# 1_1.net
KiCad netlist of a schematic drawn in Altium Designer
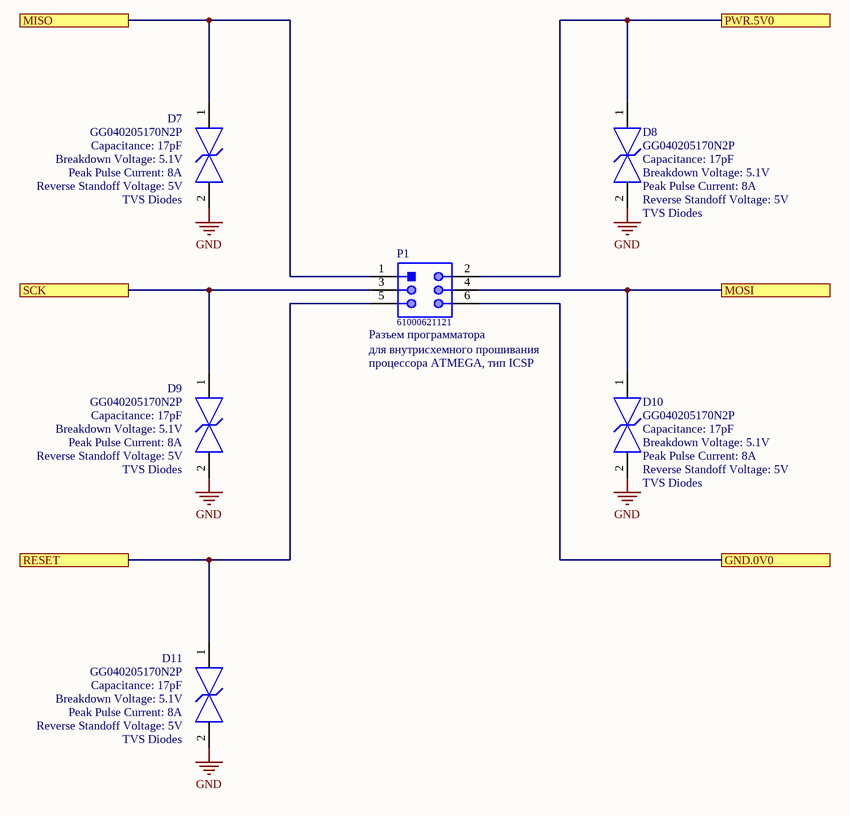
[diagram p0: Блок1.1.SchDoc]

(export (version "E")
  (design (tool "Eeschema 10.0.6"))
  (components
    (comp (ref "D7")
      (value "GG040205170N2P")
      (footprint "FP-GG0402-IPC_A")
      (description "TVS DIODE 5V 10V 0402")
      (fields
        (field (name "OCTOPART") "https://octopart.com/gg040205170n2p-avx-81066082")
        (field (name "CAPACITANCE") "17pF")
        (field (name "MANUFACTURER") "AVX")
        (field (name "BREAKDOWN VOLTAGE") "5.1V")
        (field (name "PEAK PULSE CURRENT") "8A")
        (field (name "REVERSE STANDOFF VOLTAGE") "5V")
        (field (name "DEVICE CLASS L2") "TVS Diodes")
      )
      (libsource (lib "Altium Content Vault") (part "11bd9d59d340f0612179daf16ad9b72"))
    )
    (comp (ref "D8")
      (value "GG040205170N2P")
      (footprint "FP-GG0402-IPC_A")
      (description "TVS DIODE 5V 10V 0402")
      (fields
        (field (name "OCTOPART") "https://octopart.com/gg040205170n2p-avx-81066082")
        (field (name "CAPACITANCE") "17pF")
        (field (name "MANUFACTURER") "AVX")
        (field (name "BREAKDOWN VOLTAGE") "5.1V")
        (field (name "PEAK PULSE CURRENT") "8A")
        (field (name "REVERSE STANDOFF VOLTAGE") "5V")
        (field (name "DEVICE CLASS L2") "TVS Diodes")
      )
      (libsource (lib "Altium Content Vault") (part "11bd9d59d340f0612179daf16ad9b72"))
    )
    (comp (ref "D9")
      (value "GG040205170N2P")
      (footprint "FP-GG0402-IPC_A")
      (description "TVS DIODE 5V 10V 0402")
      (fields
        (field (name "OCTOPART") "https://octopart.com/gg040205170n2p-avx-81066082")
        (field (name "CAPACITANCE") "17pF")
        (field (name "MANUFACTURER") "AVX")
        (field (name "BREAKDOWN VOLTAGE") "5.1V")
        (field (name "PEAK PULSE CURRENT") "8A")
        (field (name "REVERSE STANDOFF VOLTAGE") "5V")
        (field (name "DEVICE CLASS L2") "TVS Diodes")
      )
      (libsource (lib "Altium Content Vault") (part "11bd9d59d340f0612179daf16ad9b72"))
    )
    (comp (ref "D10")
      (value "GG040205170N2P")
      (footprint "FP-GG0402-IPC_A")
      (description "TVS DIODE 5V 10V 0402")
      (fields
        (field (name "OCTOPART") "https://octopart.com/gg040205170n2p-avx-81066082")
        (field (name "CAPACITANCE") "17pF")
        (field (name "MANUFACTURER") "AVX")
        (field (name "BREAKDOWN VOLTAGE") "5.1V")
        (field (name "PEAK PULSE CURRENT") "8A")
        (field (name "REVERSE STANDOFF VOLTAGE") "5V")
        (field (name "DEVICE CLASS L2") "TVS Diodes")
      )
      (libsource (lib "Altium Content Vault") (part "11bd9d59d340f0612179daf16ad9b72"))
    )
    (comp (ref "D11")
      (value "GG040205170N2P")
      (footprint "FP-GG0402-IPC_A")
      (description "TVS DIODE 5V 10V 0402")
      (fields
        (field (name "OCTOPART") "https://octopart.com/gg040205170n2p-avx-81066082")
        (field (name "CAPACITANCE") "17pF")
        (field (name "MANUFACTURER") "AVX")
        (field (name "BREAKDOWN VOLTAGE") "5.1V")
        (field (name "PEAK PULSE CURRENT") "8A")
        (field (name "REVERSE STANDOFF VOLTAGE") "5V")
        (field (name "DEVICE CLASS L2") "TVS Diodes")
      )
      (libsource (lib "Altium Content Vault") (part "11bd9d59d340f0612179daf16ad9b72"))
    )
    (comp (ref "P1")
      (value "61000621121")
      (footprint "61000621121")
      (description "SMT Vertical Pin Header WR-PHD, Pitch 2.54 mm, Dual Row, 6 pins")
      (fields
        (field (name "MANUFACTURER") "Wurth Elektronik")
        (field (name "PARAMETER 1") "Разъем программатора")
        (field (name "PARAMETER 2") "для внутрисхемного прошивания")
        (field (name "PARAMETER 3") "процессора ATMEGA, тип ICSP")
        (field (name "PUBLISHER") "WurthElektronik")
      )
      (libsource (lib "Altium Content Vault") (part "WE-CN-2P-M-R6"))
    )
  )
  (nets
    (net (code "1") (name "/GND.0V0") (class "Default")
      (node (ref "P1") (pin "6") (pinfunction "6_6") (pintype "passive"))
    )
    (net (code "2") (name "/MISO") (class "Default")
      (node (ref "D7") (pin "1") (pinfunction "1_1") (pintype "passive"))
      (node (ref "P1") (pin "1") (pinfunction "1_1") (pintype "passive"))
    )
    (net (code "3") (name "/MOSI") (class "Default")
      (node (ref "D10") (pin "1") (pinfunction "1_1") (pintype "passive"))
      (node (ref "P1") (pin "4") (pinfunction "4_4") (pintype "passive"))
    )
    (net (code "4") (name "/PWR.5V0") (class "Default")
      (node (ref "D8") (pin "1") (pinfunction "1_1") (pintype "passive"))
      (node (ref "P1") (pin "2") (pinfunction "2_2") (pintype "passive"))
    )
    (net (code "5") (name "/RESET") (class "Default")
      (node (ref "D11") (pin "1") (pinfunction "1_1") (pintype "passive"))
      (node (ref "P1") (pin "5") (pinfunction "5_5") (pintype "passive"))
    )
    (net (code "6") (name "/SCK") (class "Default")
      (node (ref "D9") (pin "1") (pinfunction "1_1") (pintype "passive"))
      (node (ref "P1") (pin "3") (pinfunction "3_3") (pintype "passive"))
    )
    (net (code "7") (name "GND") (class "Default")
      (node (ref "D10") (pin "2") (pinfunction "2_2") (pintype "passive"))
      (node (ref "D11") (pin "2") (pinfunction "2_2") (pintype "passive"))
      (node (ref "D7") (pin "2") (pinfunction "2_2") (pintype "passive"))
      (node (ref "D8") (pin "2") (pinfunction "2_2") (pintype "passive"))
      (node (ref "D9") (pin "2") (pinfunction "2_2") (pintype "passive"))
    )
  )
)
